# SpherebotShield.net
KiCad netlist of a schematic drawn in EAGLE
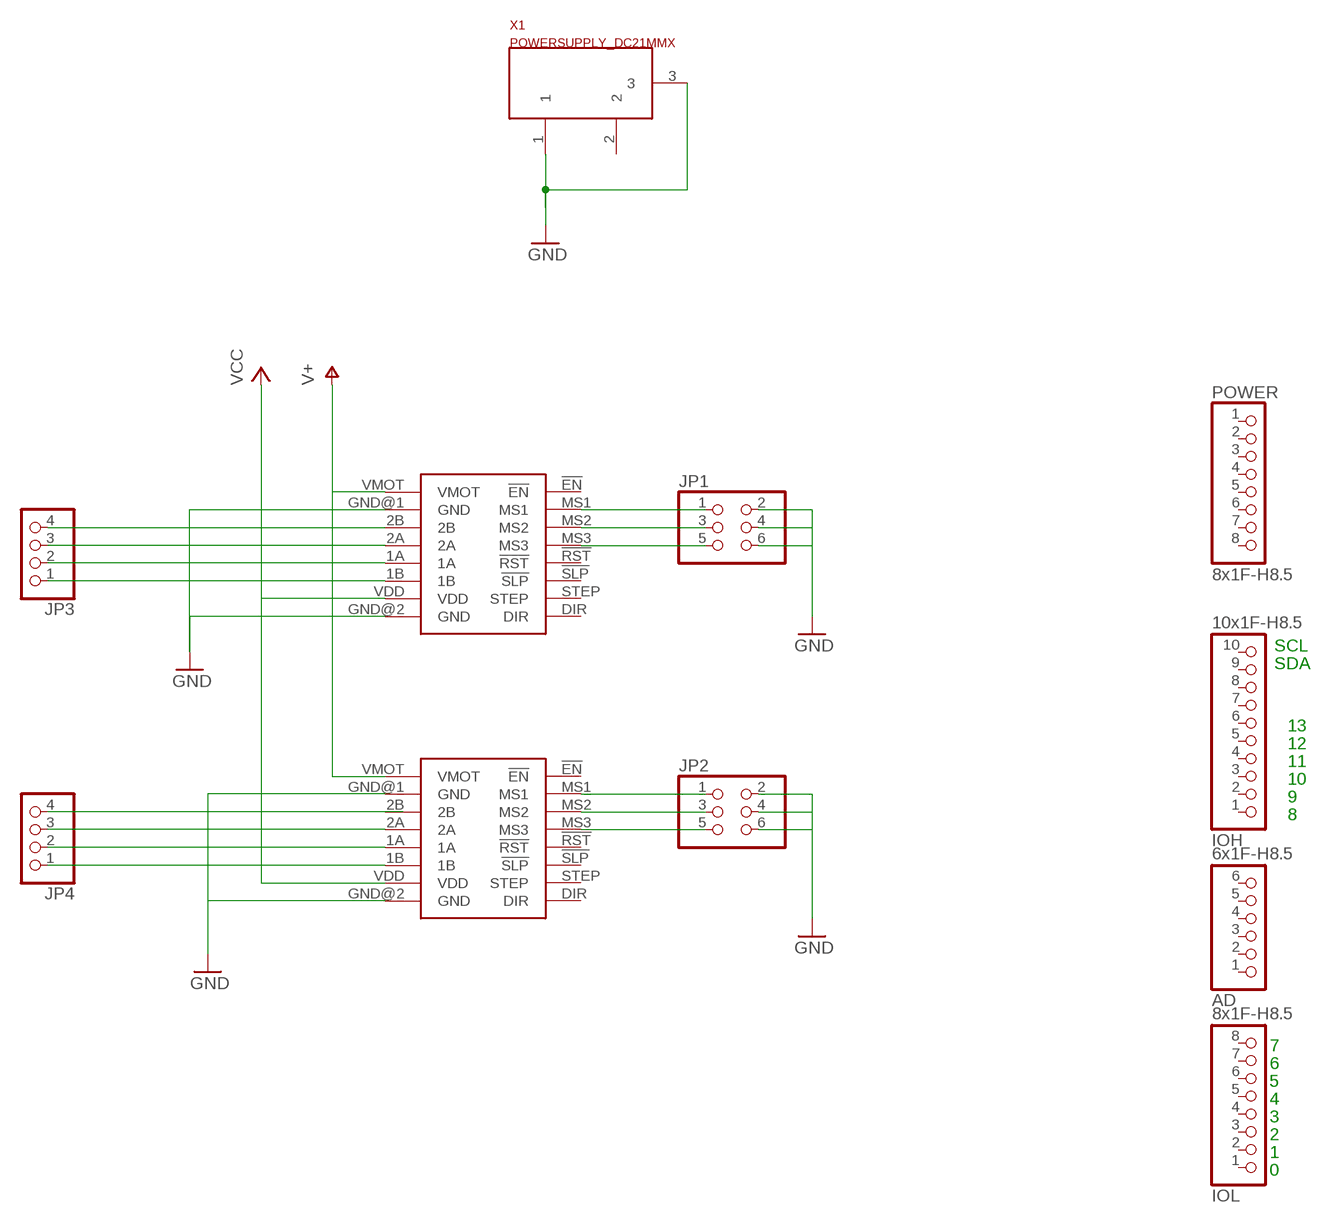
[diagram p0: schematic, sheet 1]

(export (version "E")
  (design (tool "Eeschema 10.0.6"))
  (components
    (comp (ref "AD")
      (value "6x1F-H8.5")
      (footprint "eagle-import:1X06")
      (libsource (lib "eagle-import") (part "PINHD-1X6"))
    )
    (comp (ref "IOH")
      (value "10x1F-H8.5")
      (footprint "eagle-import:1X10")
      (libsource (lib "eagle-import") (part "PINHD-1X10_ARD"))
    )
    (comp (ref "IOL")
      (value "8x1F-H8.5")
      (footprint "eagle-import:1X08")
      (libsource (lib "eagle-import") (part "PINHD-1X8"))
    )
    (comp (ref "JP1")
      (value "PINHD-2X3")
      (footprint "eagle-import:2X03")
      (libsource (lib "eagle-import") (part "PINHD-2X3"))
    )
    (comp (ref "JP2")
      (value "PINHD-2X3")
      (footprint "eagle-import:2X03")
      (libsource (lib "eagle-import") (part "PINHD-2X3"))
    )
    (comp (ref "JP3")
      (value "PINHD-1X4")
      (footprint "eagle-import:1X04")
      (libsource (lib "eagle-import") (part "PINHD-1X4"))
    )
    (comp (ref "JP4")
      (value "PINHD-1X4")
      (footprint "eagle-import:1X04")
      (libsource (lib "eagle-import") (part "PINHD-1X4"))
    )
    (comp (ref "POWER")
      (value "8x1F-H8.5")
      (footprint "eagle-import:1X08")
      (libsource (lib "eagle-import") (part "PINHD-1X8"))
    )
    (comp (ref "U$1")
      (value "STEPSTICK")
      (footprint "eagle-import:STEPSTICK")
      (libsource (lib "eagle-import") (part "STEPSTICK"))
    )
    (comp (ref "U$2")
      (value "STEPSTICK")
      (footprint "eagle-import:STEPSTICK")
      (libsource (lib "eagle-import") (part "STEPSTICK"))
    )
    (comp (ref "X1")
      (value "POWERSUPPLY_DC21MMX")
      (footprint "eagle-import:POWERSUPPLY_DC-21MM")
      (libsource (lib "eagle-import") (part "POWERSUPPLY_DC21MMX"))
    )
  )
  (nets
    (net (code "1") (name "/2") (class "Default")
      (node (ref "X1") (pin "2") (pinfunction "2_2") (pintype "power_in"))
    )
    (net (code "2") (name "GND") (class "Default")
      (node (ref "JP1") (pin "2") (pinfunction "2_2") (pintype "passive"))
      (node (ref "JP1") (pin "4") (pinfunction "4_4") (pintype "passive"))
      (node (ref "JP1") (pin "6") (pinfunction "6_6") (pintype "passive"))
      (node (ref "JP2") (pin "2") (pinfunction "2_2") (pintype "passive"))
      (node (ref "JP2") (pin "4") (pinfunction "4_4") (pintype "passive"))
      (node (ref "JP2") (pin "6") (pinfunction "6_6") (pintype "passive"))
      (node (ref "U$1") (pin "GND@1") (pinfunction "GND_GND@1") (pintype "power_in"))
      (node (ref "U$1") (pin "GND@2") (pinfunction "GND_GND@2") (pintype "bidirectional"))
      (node (ref "U$2") (pin "GND@1") (pinfunction "GND_GND@1") (pintype "power_in"))
      (node (ref "U$2") (pin "GND@2") (pinfunction "GND_GND@2") (pintype "bidirectional"))
      (node (ref "X1") (pin "1") (pinfunction "1_1") (pintype "power_in"))
      (node (ref "X1") (pin "3") (pinfunction "3_3") (pintype "power_in"))
    )
    (net (code "3") (name "Net-(JP1-Pad1)") (class "Default")
      (node (ref "JP1") (pin "1") (pinfunction "1_1") (pintype "passive"))
      (node (ref "U$1") (pin "MS1") (pinfunction "MS1_MS1") (pintype "bidirectional"))
    )
    (net (code "4") (name "Net-(JP1-Pad3)") (class "Default")
      (node (ref "JP1") (pin "3") (pinfunction "3_3") (pintype "passive"))
      (node (ref "U$1") (pin "MS2") (pinfunction "MS2_MS2") (pintype "bidirectional"))
    )
    (net (code "5") (name "Net-(JP1-Pad5)") (class "Default")
      (node (ref "JP1") (pin "5") (pinfunction "5_5") (pintype "passive"))
      (node (ref "U$1") (pin "MS3") (pinfunction "MS3_MS3") (pintype "bidirectional"))
    )
    (net (code "6") (name "Net-(JP2-Pad1)") (class "Default")
      (node (ref "JP2") (pin "1") (pinfunction "1_1") (pintype "passive"))
      (node (ref "U$2") (pin "MS1") (pinfunction "MS1_MS1") (pintype "bidirectional"))
    )
    (net (code "7") (name "Net-(JP2-Pad3)") (class "Default")
      (node (ref "JP2") (pin "3") (pinfunction "3_3") (pintype "passive"))
      (node (ref "U$2") (pin "MS2") (pinfunction "MS2_MS2") (pintype "bidirectional"))
    )
    (net (code "8") (name "Net-(JP2-Pad5)") (class "Default")
      (node (ref "JP2") (pin "5") (pinfunction "5_5") (pintype "passive"))
      (node (ref "U$2") (pin "MS3") (pinfunction "MS3_MS3") (pintype "bidirectional"))
    )
    (net (code "9") (name "Net-(JP3-Pad1)") (class "Default")
      (node (ref "JP3") (pin "1") (pinfunction "1_1") (pintype "passive"))
      (node (ref "U$1") (pin "1B") (pinfunction "1B_1B") (pintype "output"))
    )
    (net (code "10") (name "Net-(JP3-Pad2)") (class "Default")
      (node (ref "JP3") (pin "2") (pinfunction "2_2") (pintype "passive"))
      (node (ref "U$1") (pin "1A") (pinfunction "1A_1A") (pintype "output"))
    )
    (net (code "11") (name "Net-(JP3-Pad3)") (class "Default")
      (node (ref "JP3") (pin "3") (pinfunction "3_3") (pintype "passive"))
      (node (ref "U$1") (pin "2A") (pinfunction "2A_2A") (pintype "output"))
    )
    (net (code "12") (name "Net-(JP3-Pad4)") (class "Default")
      (node (ref "JP3") (pin "4") (pinfunction "4_4") (pintype "passive"))
      (node (ref "U$1") (pin "2B") (pinfunction "2B_2B") (pintype "output"))
    )
    (net (code "13") (name "Net-(JP4-Pad1)") (class "Default")
      (node (ref "JP4") (pin "1") (pinfunction "1_1") (pintype "passive"))
      (node (ref "U$2") (pin "1B") (pinfunction "1B_1B") (pintype "output"))
    )
    (net (code "14") (name "Net-(JP4-Pad2)") (class "Default")
      (node (ref "JP4") (pin "2") (pinfunction "2_2") (pintype "passive"))
      (node (ref "U$2") (pin "1A") (pinfunction "1A_1A") (pintype "output"))
    )
    (net (code "15") (name "Net-(JP4-Pad3)") (class "Default")
      (node (ref "JP4") (pin "3") (pinfunction "3_3") (pintype "passive"))
      (node (ref "U$2") (pin "2A") (pinfunction "2A_2A") (pintype "output"))
    )
    (net (code "16") (name "V+") (class "Default")
      (node (ref "U$1") (pin "VMOT") (pinfunction "VMOT_VMOT") (pintype "power_in"))
      (node (ref "U$2") (pin "VMOT") (pinfunction "VMOT_VMOT") (pintype "power_in"))
    )
    (net (code "17") (name "VCC") (class "Default")
      (node (ref "U$1") (pin "VDD") (pinfunction "VDD_VDD") (pintype "bidirectional"))
      (node (ref "U$2") (pin "VDD") (pinfunction "VDD_VDD") (pintype "bidirectional"))
    )
    (net (code "18") (name "unconnected-(AD-Pad1)") (class "Default")
      (node (ref "AD") (pin "1") (pinfunction "1_1") (pintype "passive"))
    )
    (net (code "19") (name "unconnected-(AD-Pad2)") (class "Default")
      (node (ref "AD") (pin "2") (pinfunction "2_2") (pintype "passive"))
    )
    (net (code "20") (name "unconnected-(AD-Pad3)") (class "Default")
      (node (ref "AD") (pin "3") (pinfunction "3_3") (pintype "passive"))
    )
    (net (code "21") (name "unconnected-(AD-Pad4)") (class "Default")
      (node (ref "AD") (pin "4") (pinfunction "4_4") (pintype "passive"))
    )
    (net (code "22") (name "unconnected-(AD-Pad5)") (class "Default")
      (node (ref "AD") (pin "5") (pinfunction "5_5") (pintype "passive"))
    )
    (net (code "23") (name "unconnected-(AD-Pad6)") (class "Default")
      (node (ref "AD") (pin "6") (pinfunction "6_6") (pintype "passive"))
    )
    (net (code "24") (name "unconnected-(IOH-Pad1)") (class "Default")
      (node (ref "IOH") (pin "1") (pinfunction "1_1") (pintype "passive"))
    )
    (net (code "25") (name "unconnected-(IOH-Pad2)") (class "Default")
      (node (ref "IOH") (pin "2") (pinfunction "2_2") (pintype "passive"))
    )
    (net (code "26") (name "unconnected-(IOH-Pad3)") (class "Default")
      (node (ref "IOH") (pin "3") (pinfunction "3_3") (pintype "passive"))
    )
    (net (code "27") (name "unconnected-(IOH-Pad4)") (class "Default")
      (node (ref "IOH") (pin "4") (pinfunction "4_4") (pintype "passive"))
    )
    (net (code "28") (name "unconnected-(IOH-Pad5)") (class "Default")
      (node (ref "IOH") (pin "5") (pinfunction "5_5") (pintype "passive"))
    )
    (net (code "29") (name "unconnected-(IOH-Pad6)") (class "Default")
      (node (ref "IOH") (pin "6") (pinfunction "6_6") (pintype "passive"))
    )
    (net (code "30") (name "unconnected-(IOH-Pad7)") (class "Default")
      (node (ref "IOH") (pin "7") (pinfunction "7_7") (pintype "passive"))
    )
    (net (code "31") (name "unconnected-(IOH-Pad8)") (class "Default")
      (node (ref "IOH") (pin "8") (pinfunction "8_8") (pintype "passive"))
    )
    (net (code "32") (name "unconnected-(IOH-Pad9)") (class "Default")
      (node (ref "IOH") (pin "9") (pinfunction "9_9") (pintype "passive"))
    )
    (net (code "33") (name "unconnected-(IOH-Pad10)") (class "Default")
      (node (ref "IOH") (pin "10") (pinfunction "10_10") (pintype "passive"))
    )
    (net (code "34") (name "unconnected-(IOL-Pad1)") (class "Default")
      (node (ref "IOL") (pin "1") (pinfunction "1_1") (pintype "passive"))
    )
    (net (code "35") (name "unconnected-(IOL-Pad2)") (class "Default")
      (node (ref "IOL") (pin "2") (pinfunction "2_2") (pintype "passive"))
    )
    (net (code "36") (name "unconnected-(IOL-Pad3)") (class "Default")
      (node (ref "IOL") (pin "3") (pinfunction "3_3") (pintype "passive"))
    )
    (net (code "37") (name "unconnected-(IOL-Pad4)") (class "Default")
      (node (ref "IOL") (pin "4") (pinfunction "4_4") (pintype "passive"))
    )
    (net (code "38") (name "unconnected-(IOL-Pad5)") (class "Default")
      (node (ref "IOL") (pin "5") (pinfunction "5_5") (pintype "passive"))
    )
    (net (code "39") (name "unconnected-(IOL-Pad6)") (class "Default")
      (node (ref "IOL") (pin "6") (pinfunction "6_6") (pintype "passive"))
    )
    (net (code "40") (name "unconnected-(IOL-Pad7)") (class "Default")
      (node (ref "IOL") (pin "7") (pinfunction "7_7") (pintype "passive"))
    )
    (net (code "41") (name "unconnected-(IOL-Pad8)") (class "Default")
      (node (ref "IOL") (pin "8") (pinfunction "8_8") (pintype "passive"))
    )
    (net (code "42") (name "unconnected-(JP4-Pad4)") (class "Default")
      (node (ref "JP4") (pin "4") (pinfunction "4_4") (pintype "passive"))
    )
    (net (code "43") (name "unconnected-(POWER-Pad1)") (class "Default")
      (node (ref "POWER") (pin "1") (pinfunction "1_1") (pintype "passive"))
    )
    (net (code "44") (name "unconnected-(POWER-Pad2)") (class "Default")
      (node (ref "POWER") (pin "2") (pinfunction "2_2") (pintype "passive"))
    )
    (net (code "45") (name "unconnected-(POWER-Pad3)") (class "Default")
      (node (ref "POWER") (pin "3") (pinfunction "3_3") (pintype "passive"))
    )
    (net (code "46") (name "unconnected-(POWER-Pad4)") (class "Default")
      (node (ref "POWER") (pin "4") (pinfunction "4_4") (pintype "passive"))
    )
    (net (code "47") (name "unconnected-(POWER-Pad5)") (class "Default")
      (node (ref "POWER") (pin "5") (pinfunction "5_5") (pintype "passive"))
    )
    (net (code "48") (name "unconnected-(POWER-Pad6)") (class "Default")
      (node (ref "POWER") (pin "6") (pinfunction "6_6") (pintype "passive"))
    )
    (net (code "49") (name "unconnected-(POWER-Pad7)") (class "Default")
      (node (ref "POWER") (pin "7") (pinfunction "7_7") (pintype "passive"))
    )
    (net (code "50") (name "unconnected-(POWER-Pad8)") (class "Default")
      (node (ref "POWER") (pin "8") (pinfunction "8_8") (pintype "passive"))
    )
    (net (code "51") (name "unconnected-(U$1-PadDIR)") (class "Default")
      (node (ref "U$1") (pin "DIR") (pinfunction "DIR_DIR") (pintype "bidirectional"))
    )
    (net (code "52") (name "unconnected-(U$1-PadSTEP)") (class "Default")
      (node (ref "U$1") (pin "STEP") (pinfunction "STEP_STEP") (pintype "bidirectional"))
    )
    (net (code "53") (name "unconnected-(U$1-~{EN}-Pad!EN)") (class "Default")
      (node (ref "U$1") (pin "!EN") (pinfunction "~{EN}_!EN") (pintype "bidirectional"))
    )
    (net (code "54") (name "unconnected-(U$1-~{RST}-Pad!RST)") (class "Default")
      (node (ref "U$1") (pin "!RST") (pinfunction "~{RST}_!RST") (pintype "bidirectional"))
    )
    (net (code "55") (name "unconnected-(U$1-~{SLP}-Pad!SLP)") (class "Default")
      (node (ref "U$1") (pin "!SLP") (pinfunction "~{SLP}_!SLP") (pintype "bidirectional"))
    )
    (net (code "56") (name "unconnected-(U$2-Pad2B)") (class "Default")
      (node (ref "U$2") (pin "2B") (pinfunction "2B_2B") (pintype "output"))
    )
    (net (code "57") (name "unconnected-(U$2-PadDIR)") (class "Default")
      (node (ref "U$2") (pin "DIR") (pinfunction "DIR_DIR") (pintype "bidirectional"))
    )
    (net (code "58") (name "unconnected-(U$2-PadSTEP)") (class "Default")
      (node (ref "U$2") (pin "STEP") (pinfunction "STEP_STEP") (pintype "bidirectional"))
    )
    (net (code "59") (name "unconnected-(U$2-~{EN}-Pad!EN)") (class "Default")
      (node (ref "U$2") (pin "!EN") (pinfunction "~{EN}_!EN") (pintype "bidirectional"))
    )
    (net (code "60") (name "unconnected-(U$2-~{RST}-Pad!RST)") (class "Default")
      (node (ref "U$2") (pin "!RST") (pinfunction "~{RST}_!RST") (pintype "bidirectional"))
    )
    (net (code "61") (name "unconnected-(U$2-~{SLP}-Pad!SLP)") (class "Default")
      (node (ref "U$2") (pin "!SLP") (pinfunction "~{SLP}_!SLP") (pintype "bidirectional"))
    )
  )
)
